# MAIN_LORA_ANT.net
KiCad netlist of a schematic drawn in Altium Designer
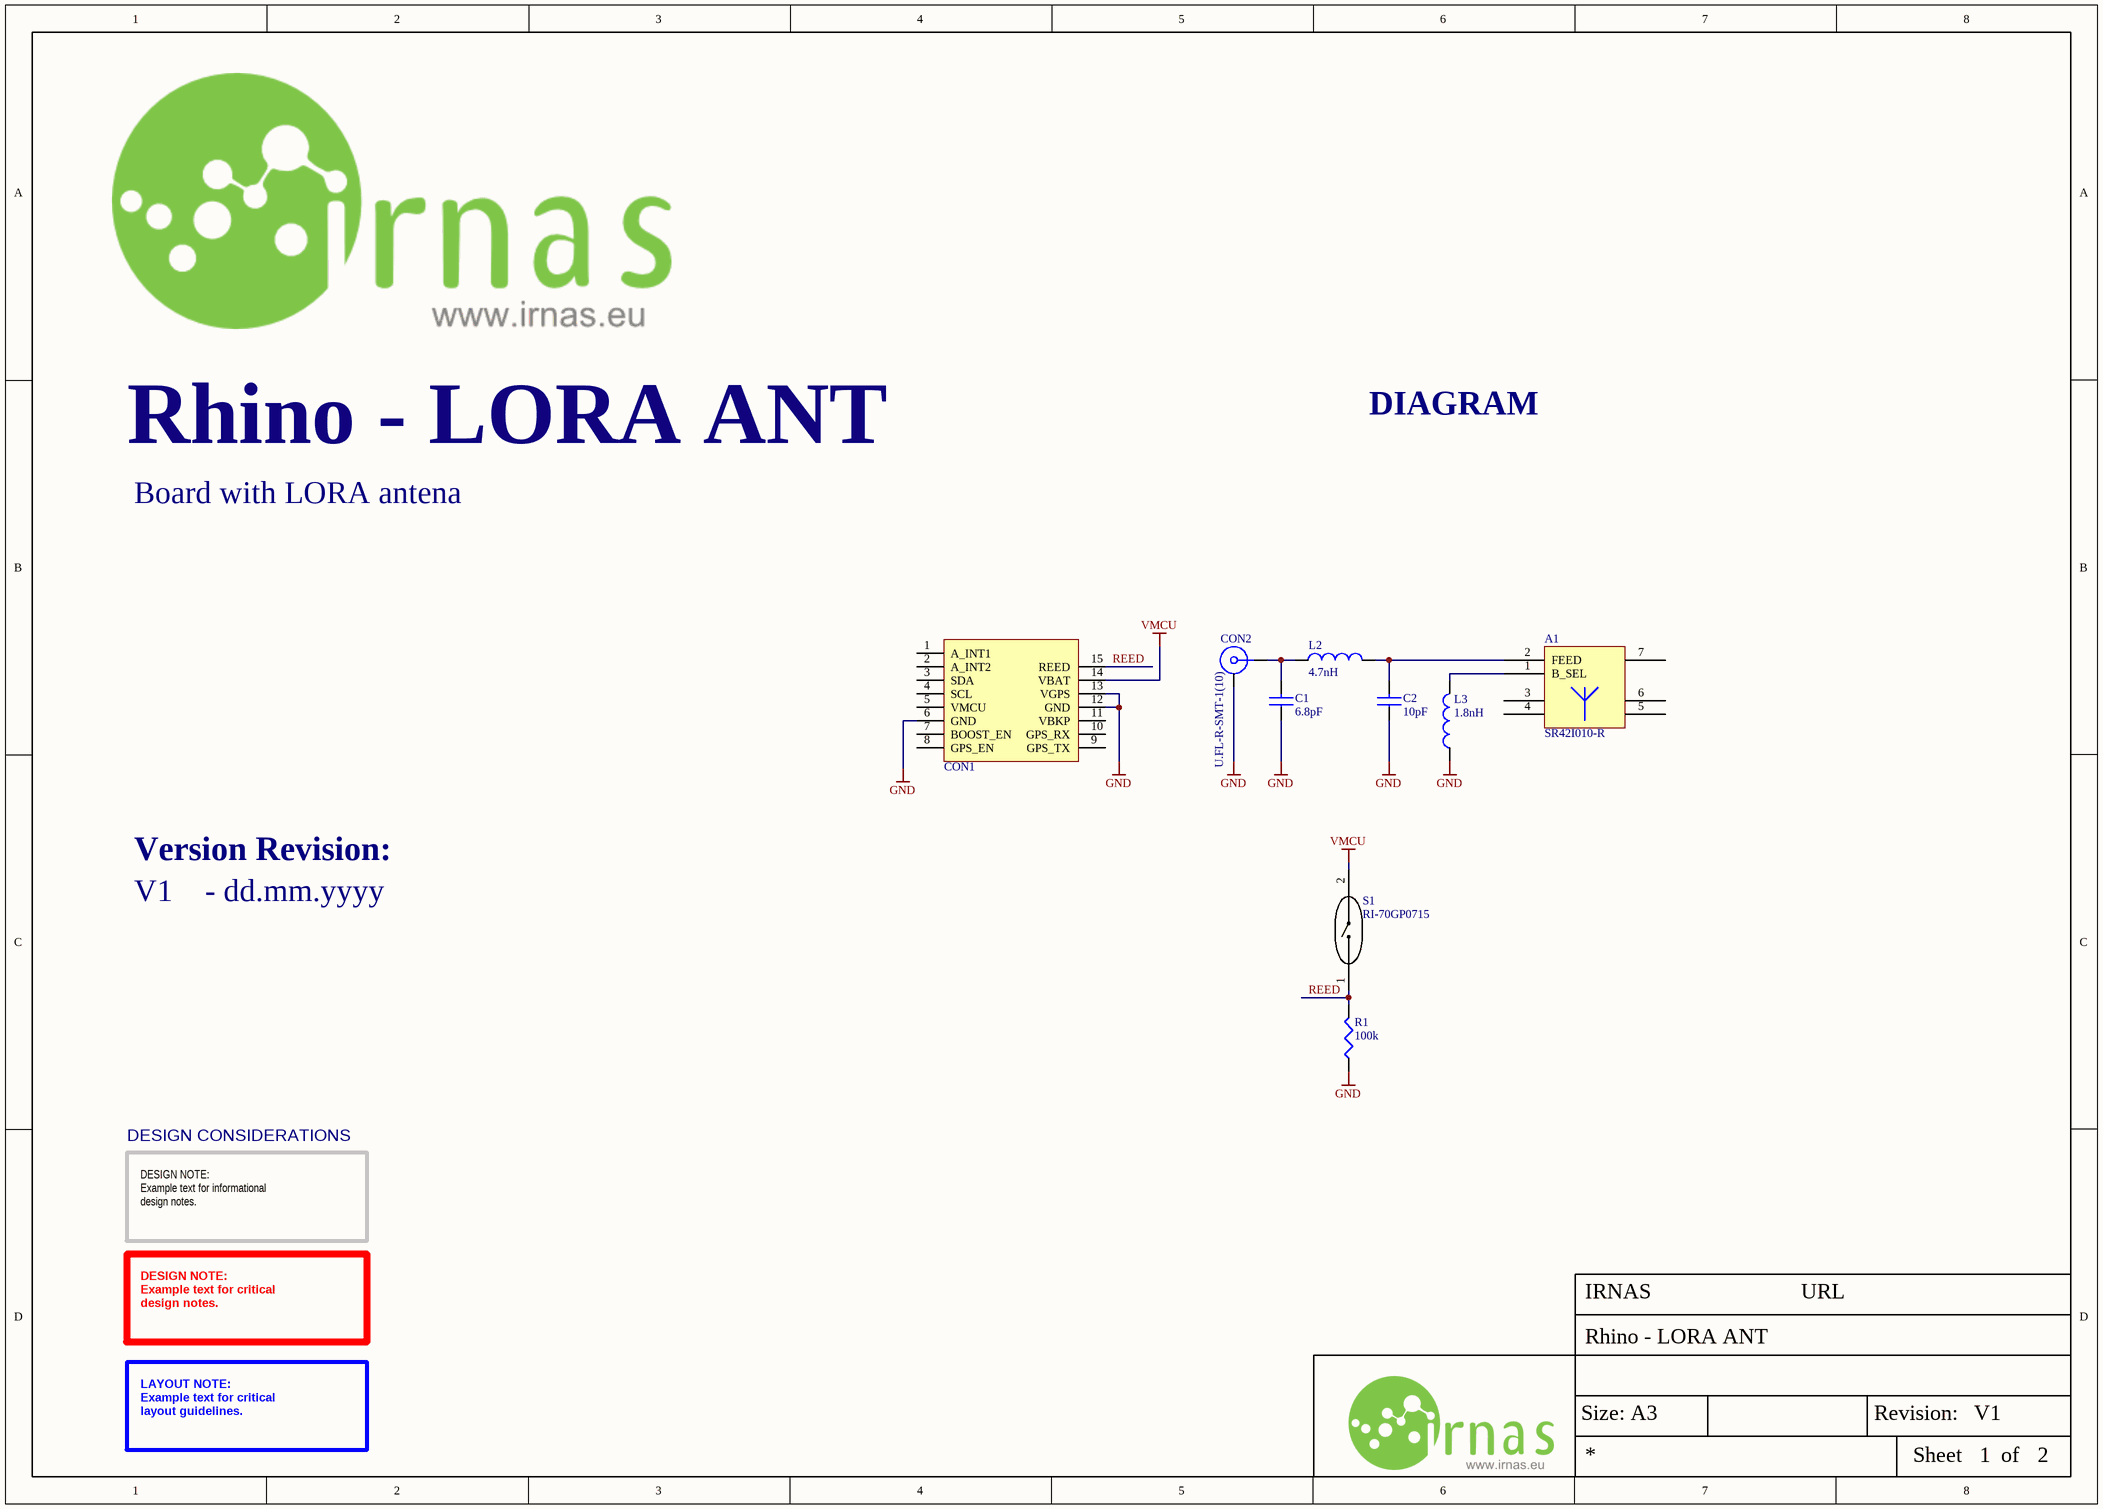
[diagram p0: MAIN_LORA_ANT.SchDoc]

(export (version "E")
  (design (tool "Eeschema 10.0.6"))
  (components
    (comp (ref "A1")
      (value "SR42I010-R")
      (footprint "LORA_PCB_ANTENNA")
      (description "Antenna SMD -4dBi Gain 870MHz/928MHz Automotive 7-Pin SMD T/R")
      (fields (field (name "MANUFACTURER") "Antenova"))
      (libsource (lib "Passive") (part "ANT - SR42I010-R"))
    )
    (comp (ref "C1")
      (value "6.8pF")
      (footprint "CAP0402")
      (description "Multilayer Ceramic Capacitors MLCC - SMD/SMT 50volts 1.8pF C0G")
      (fields
        (field (name "MANUFACTURER") "KEMET")
        (field (name "MANUFACTURER PART NUMBER") "C0402C189B5GACTU")
      )
      (libsource (lib "Passive") (part "C - 1.8pF/0402"))
    )
    (comp (ref "C2")
      (value "10pF")
      (footprint "CAP0402")
      (description "Multilayer Ceramic Capacitors MLCC - SMD/SMT 50volts 1.8pF C0G")
      (fields
        (field (name "MANUFACTURER") "KEMET")
        (field (name "MANUFACTURER PART NUMBER") "C0402C189B5GACTU")
      )
      (libsource (lib "Passive") (part "C - 1.8pF/0402"))
    )
    (comp (ref "CON1")
      (value "Between PCB connection")
      (footprint "SmartParks_Rhino")
      (libsource (lib "Connectors") (part "SmartParks_Rhino"))
    )
    (comp (ref "CON2")
      (value "U.FL-R-SMT-1(10)")
      (footprint "ufl connector smd")
      (description "RF / Coaxial Connector, U.FL Coaxial, Straight Jack, Surface Mount Vertical, 50 ohm, Brass")
      (fields (field (name "MANUFACTURER") "Hirose"))
      (libsource (lib "Connectors") (part "U.FL-R-SMT-1(10)"))
    )
    (comp (ref "L2")
      (value "4.7nH")
      (footprint "IND0402")
      (description "Inductor RF Chip Multi-Layer 4.3nH 0.3nH 100MHz 8Q-Factor Air 300mA 210mOhm DCR 0402 Paper T/R")
      (fields
        (field (name "MANUFACTURER") "Murata")
        (field (name "MANUFACTURER PART NUMBER") "LQG15HN4N3S02D")
      )
      (libsource (lib "Passive") (part "L - 4.3nH/0402"))
    )
    (comp (ref "L3")
      (value "1.8nH")
      (footprint "IND0402")
      (description "Inductor RF Chip Multi-Layer 4.3nH 0.3nH 100MHz 8Q-Factor Air 300mA 210mOhm DCR 0402 Paper T/R")
      (fields
        (field (name "MANUFACTURER") "Murata")
        (field (name "MANUFACTURER PART NUMBER") "LQG15HN4N3S02D")
      )
      (libsource (lib "Passive") (part "L - 4.3nH/0402"))
    )
    (comp (ref "R1")
      (value "100k")
      (footprint "RES0402")
      (description "MULTICOMP   MCWR04X1003FTL   RES, THICK FILM, 100KOHM, 1%, 0.0625W")
      (fields
        (field (name "MANUFACTURER") "Multicomp")
        (field (name "MANUFACTURER PART NUMBER") "MCWR04X1003FTL")
      )
      (libsource (lib "Passive") (part "R - 100k/0402"))
    )
    (comp (ref "S1")
      (value "RI-70GP0715")
      (footprint "RI-70GP0715")
      (libsource (lib "Mechanical") (part "Reed Switch"))
    )
  )
  (nets
    (net (code "1") (name "/REED") (class "Default")
      (node (ref "CON1") (pin "15") (pinfunction "REED_15") (pintype "passive"))
      (node (ref "R1") (pin "2") (pinfunction "2_2") (pintype "passive"))
      (node (ref "S1") (pin "1") (pinfunction "1_1") (pintype "passive"))
    )
    (net (code "2") (name "GND") (class "Default")
      (node (ref "C1") (pin "1") (pinfunction "1_1") (pintype "passive"))
      (node (ref "C2") (pin "1") (pinfunction "1_1") (pintype "passive"))
      (node (ref "CON1") (pin "12") (pinfunction "GND_12") (pintype "passive"))
      (node (ref "CON1") (pin "13") (pinfunction "VGPS_13") (pintype "passive"))
      (node (ref "CON1") (pin "6") (pinfunction "GND_6") (pintype "passive"))
      (node (ref "CON2") (pin "2") (pinfunction "2_2") (pintype "open_collector"))
      (node (ref "L3") (pin "1") (pinfunction "1_1") (pintype "passive"))
      (node (ref "R1") (pin "1") (pinfunction "1_1") (pintype "passive"))
    )
    (net (code "3") (name "Net-(A1-B_SEL)") (class "Default")
      (node (ref "A1") (pin "1") (pinfunction "B_SEL_1") (pintype "passive"))
      (node (ref "L3") (pin "2") (pinfunction "2_2") (pintype "passive"))
    )
    (net (code "4") (name "Net-(A1-FEED)") (class "Default")
      (node (ref "A1") (pin "2") (pinfunction "FEED_2") (pintype "passive"))
      (node (ref "C2") (pin "2") (pinfunction "2_2") (pintype "passive"))
      (node (ref "L2") (pin "2") (pinfunction "2_2") (pintype "passive"))
    )
    (net (code "5") (name "Net-(C1-Pad2)") (class "Default")
      (node (ref "C1") (pin "2") (pinfunction "2_2") (pintype "passive"))
      (node (ref "CON2") (pin "1") (pinfunction "1_1") (pintype "open_collector"))
      (node (ref "L2") (pin "1") (pinfunction "1_1") (pintype "passive"))
    )
    (net (code "6") (name "VMCU") (class "Default")
      (node (ref "CON1") (pin "14") (pinfunction "VBAT_14") (pintype "passive"))
      (node (ref "S1") (pin "2") (pinfunction "2_2") (pintype "passive"))
    )
    (net (code "7") (name "unconnected-(A1-Pad3)") (class "Default")
      (node (ref "A1") (pin "3") (pintype "passive"))
    )
    (net (code "8") (name "unconnected-(A1-Pad4)") (class "Default")
      (node (ref "A1") (pin "4") (pintype "passive"))
    )
    (net (code "9") (name "unconnected-(A1-Pad5)") (class "Default")
      (node (ref "A1") (pin "5") (pintype "passive"))
    )
    (net (code "10") (name "unconnected-(A1-Pad6)") (class "Default")
      (node (ref "A1") (pin "6") (pintype "passive"))
    )
    (net (code "11") (name "unconnected-(A1-Pad7)") (class "Default")
      (node (ref "A1") (pin "7") (pintype "passive"))
    )
    (net (code "12") (name "unconnected-(CON1-A_INT1-Pad1)") (class "Default")
      (node (ref "CON1") (pin "1") (pinfunction "A_INT1_1") (pintype "passive"))
    )
    (net (code "13") (name "unconnected-(CON1-A_INT2-Pad2)") (class "Default")
      (node (ref "CON1") (pin "2") (pinfunction "A_INT2_2") (pintype "passive"))
    )
    (net (code "14") (name "unconnected-(CON1-BOOST_EN-Pad7)") (class "Default")
      (node (ref "CON1") (pin "7") (pinfunction "BOOST_EN_7") (pintype "passive"))
    )
    (net (code "15") (name "unconnected-(CON1-GPS_EN-Pad8)") (class "Default")
      (node (ref "CON1") (pin "8") (pinfunction "GPS_EN_8") (pintype "passive"))
    )
    (net (code "16") (name "unconnected-(CON1-GPS_RX-Pad10)") (class "Default")
      (node (ref "CON1") (pin "10") (pinfunction "GPS_RX_10") (pintype "passive"))
    )
    (net (code "17") (name "unconnected-(CON1-GPS_TX-Pad9)") (class "Default")
      (node (ref "CON1") (pin "9") (pinfunction "GPS_TX_9") (pintype "passive"))
    )
    (net (code "18") (name "unconnected-(CON1-SCL-Pad4)") (class "Default")
      (node (ref "CON1") (pin "4") (pinfunction "SCL_4") (pintype "passive"))
    )
    (net (code "19") (name "unconnected-(CON1-SDA-Pad3)") (class "Default")
      (node (ref "CON1") (pin "3") (pinfunction "SDA_3") (pintype "passive"))
    )
    (net (code "20") (name "unconnected-(CON1-VBKP-Pad11)") (class "Default")
      (node (ref "CON1") (pin "11") (pinfunction "VBKP_11") (pintype "passive"))
    )
    (net (code "21") (name "unconnected-(CON1-VMCU-Pad5)") (class "Default")
      (node (ref "CON1") (pin "5") (pinfunction "VMCU_5") (pintype "passive"))
    )
  )
)
